# MACH32.net
KiCad netlist of a schematic drawn in EAGLE
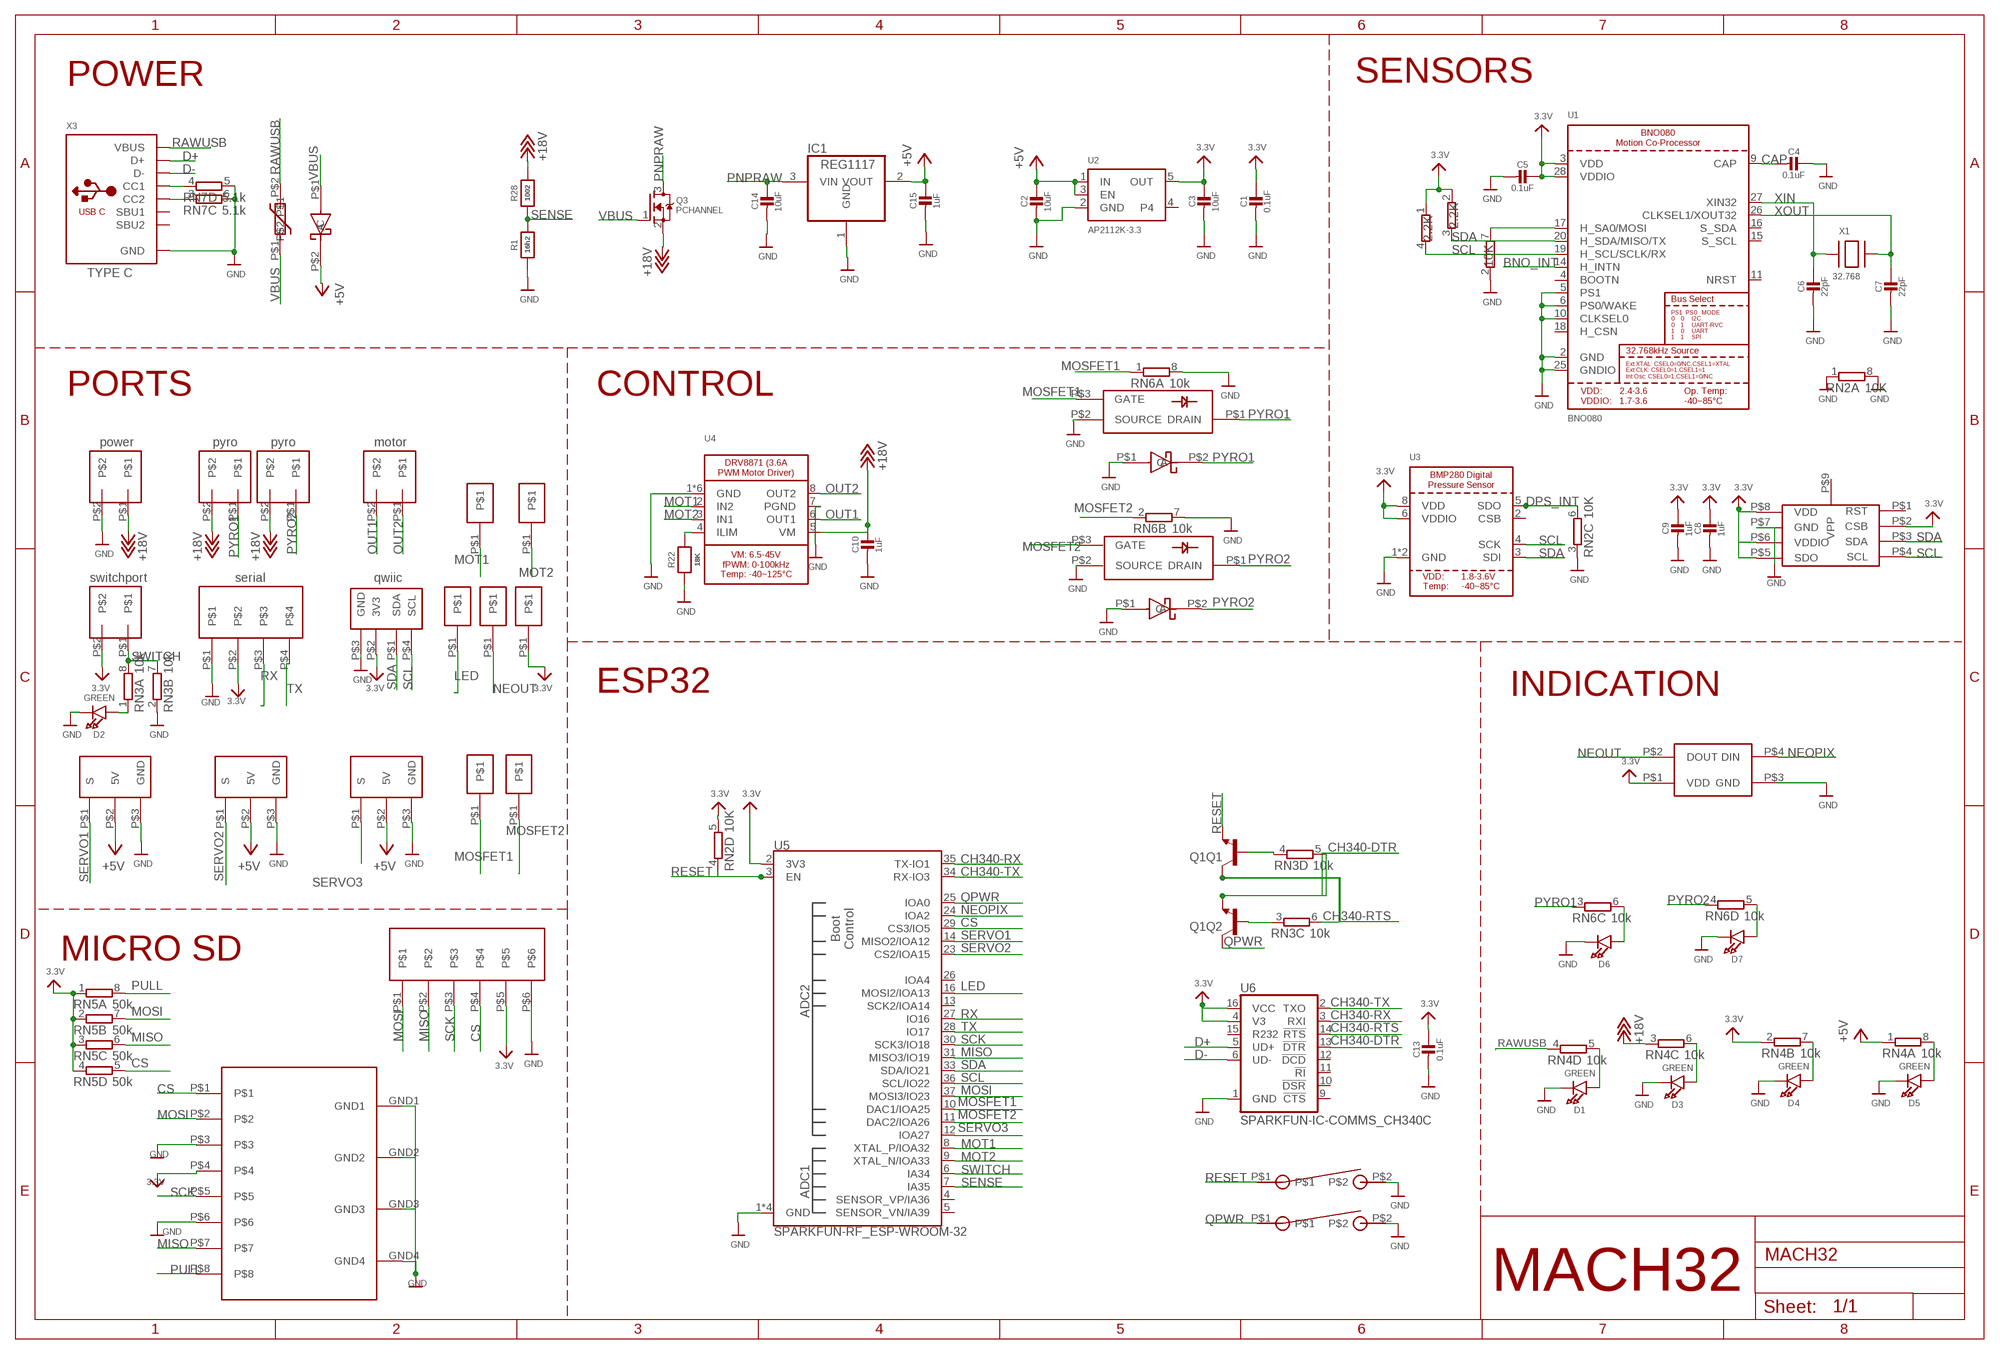
[diagram p0: schematic, sheet 1]

(export (version "E")
  (design (tool "Eeschema 10.0.6"))
  (components
    (comp (ref "C1")
      (value "0.1uF")
      (footprint "eagle-import:0603-NO")
      (libsource (lib "eagle-import") (part "CAP_CERAMIC0603_NO"))
    )
    (comp (ref "C2")
      (value "10uF")
      (footprint "eagle-import:0805-NO")
      (libsource (lib "eagle-import") (part "CAP_CERAMIC0805-NOOUTLINE"))
    )
    (comp (ref "C3")
      (value "10uF")
      (footprint "eagle-import:0805-NO")
      (libsource (lib "eagle-import") (part "CAP_CERAMIC0805-NOOUTLINE"))
    )
    (comp (ref "C4")
      (value "0.1uF")
      (footprint "eagle-import:0603-NO")
      (libsource (lib "eagle-import") (part "CAP_CERAMIC0603_NO"))
    )
    (comp (ref "C5")
      (value "0.1uF")
      (footprint "eagle-import:0603-NO")
      (libsource (lib "eagle-import") (part "CAP_CERAMIC0603_NO"))
    )
    (comp (ref "C6")
      (value "22pF")
      (footprint "eagle-import:0603-NO")
      (libsource (lib "eagle-import") (part "CAP_CERAMIC0603_NO"))
    )
    (comp (ref "C7")
      (value "22pF")
      (footprint "eagle-import:0603-NO")
      (libsource (lib "eagle-import") (part "CAP_CERAMIC0603_NO"))
    )
    (comp (ref "C8")
      (value "1uF")
      (footprint "eagle-import:0603-NO")
      (libsource (lib "eagle-import") (part "CAP_CERAMIC0603_NO"))
    )
    (comp (ref "C9")
      (value "1uF")
      (footprint "eagle-import:0603-NO")
      (libsource (lib "eagle-import") (part "CAP_CERAMIC0603_NO"))
    )
    (comp (ref "C10")
      (value "1uF")
      (footprint "eagle-import:0603-NO")
      (libsource (lib "eagle-import") (part "CAP_CERAMIC0603_NO"))
    )
    (comp (ref "C13")
      (value "0.1uF")
      (footprint "eagle-import:0603-NO")
      (libsource (lib "eagle-import") (part "CAP_CERAMIC0603_NO"))
    )
    (comp (ref "C14")
      (value "10uF")
      (footprint "eagle-import:0805-NO")
      (libsource (lib "eagle-import") (part "CAP_CERAMIC0805-NOOUTLINE"))
    )
    (comp (ref "C15")
      (value "1uF")
      (footprint "eagle-import:0603-NO")
      (libsource (lib "eagle-import") (part "CAP_CERAMIC0603_NO"))
    )
    (comp (ref "D1")
      (value "GREEN")
      (footprint "eagle-import:CHIPLED_0603_NOOUTLINE")
      (libsource (lib "eagle-import") (part "LED0603_NOOUTLINE"))
    )
    (comp (ref "D2")
      (value "GREEN")
      (footprint "eagle-import:CHIPLED_0603_NOOUTLINE")
      (libsource (lib "eagle-import") (part "LED0603_NOOUTLINE"))
    )
    (comp (ref "D3")
      (value "GREEN")
      (footprint "eagle-import:CHIPLED_0603_NOOUTLINE")
      (libsource (lib "eagle-import") (part "LED0603_NOOUTLINE"))
    )
    (comp (ref "D4")
      (value "GREEN")
      (footprint "eagle-import:CHIPLED_0603_NOOUTLINE")
      (libsource (lib "eagle-import") (part "LED0603_NOOUTLINE"))
    )
    (comp (ref "D5")
      (value "GREEN")
      (footprint "eagle-import:CHIPLED_0603_NOOUTLINE")
      (libsource (lib "eagle-import") (part "LED0603_NOOUTLINE"))
    )
    (comp (ref "D6")
      (value "GREEN")
      (footprint "eagle-import:CHIPLED_0603_NOOUTLINE")
      (libsource (lib "eagle-import") (part "LED0603_NOOUTLINE"))
    )
    (comp (ref "D7")
      (value "GREEN")
      (footprint "eagle-import:CHIPLED_0603_NOOUTLINE")
      (fields (field (name "SPICEPREFIX") "D"))
      (libsource (lib "eagle-import") (part "LED0603_NOOUTLINE"))
    )
    (comp (ref "GENERALDIODE")
      (value "PG-TSDSON-8-32")
      (footprint "eagle-import:BSZ036NE2LSATMA1")
      (libsource (lib "eagle-import") (part "PG-TSDSON-8-32"))
    )
    (comp (ref "GENERALDIODE2")
      (value "PG-TSDSON-8-32")
      (footprint "eagle-import:BSZ036NE2LSATMA1")
      (libsource (lib "eagle-import") (part "PG-TSDSON-8-32"))
    )
    (comp (ref "IC1")
      (value "REG1117")
      (footprint "eagle-import:SOT223")
      (libsource (lib "eagle-import") (part "REG1117"))
    )
    (comp (ref "Q1")
      (value "SPARKFUN-DISCRETESEMI_TRANS_NPN_DUAL-MBT3904DW1T1")
      (footprint "eagle-import:SPARKFUN-DISCRETESEMI_SC70-6")
      (libsource (lib "eagle-import") (part "SPARKFUN-DISCRETESEMI_TRANS_NPN_DUAL-MBT3904DW1T1"))
    )
    (comp (ref "Q3")
      (value "PCHANNEL")
      (footprint "eagle-import:SOT23")
      (libsource (lib "eagle-import") (part "MOSFET-NREFLOW"))
    )
    (comp (ref "R1")
      (value "16h2")
      (footprint "eagle-import:MICROBUILDER__1206MP")
      (libsource (lib "eagle-import") (part "MICROBUILDER_RESISTOR_1206MP"))
    )
    (comp (ref "R22")
      (value "18K")
      (footprint "eagle-import:MICROBUILDER__0603MP")
      (libsource (lib "eagle-import") (part "MICROBUILDER_RESISTOR_0603MP"))
    )
    (comp (ref "R28")
      (value "1002")
      (footprint "eagle-import:MICROBUILDER__1206MP")
      (libsource (lib "eagle-import") (part "MICROBUILDER_RESISTOR_1206MP"))
    )
    (comp (ref "RN1")
      (value "2.2K")
      (footprint "eagle-import:EXB34V")
      (libsource (lib "eagle-import") (part "2R-NEXB34V"))
    )
    (comp (ref "RN2")
      (value "10K")
      (footprint "eagle-import:EXB38V")
      (libsource (lib "eagle-import") (part "4R-NEXB38V"))
    )
    (comp (ref "RN3")
      (value "10k")
      (footprint "eagle-import:EXB38V")
      (fields (field (name "SPICEPREFIX") "R"))
      (libsource (lib "eagle-import") (part "4R-NEXB38V"))
    )
    (comp (ref "RN4")
      (value "10k")
      (footprint "eagle-import:EXB38V")
      (libsource (lib "eagle-import") (part "4R-NEXB38V"))
    )
    (comp (ref "RN5")
      (value "50k")
      (footprint "eagle-import:EXB38V")
      (fields (field (name "SPICEPREFIX") "R"))
      (libsource (lib "eagle-import") (part "4R-NEXB38V"))
    )
    (comp (ref "RN6")
      (value "10k")
      (footprint "eagle-import:EXB38V")
      (libsource (lib "eagle-import") (part "4R-NEXB38V"))
    )
    (comp (ref "RN7")
      (value "5.1k")
      (footprint "eagle-import:EXB38V")
      (libsource (lib "eagle-import") (part "4R-NEXB38V"))
    )
    (comp (ref "U$17")
      (value "2SMPB-02E")
      (footprint "eagle-import:2021")
      (libsource (lib "eagle-import") (part "2SMPB-02E"))
    )
    (comp (ref "U$25")
      (value "OSTTEXX0104")
      (footprint "eagle-import:OSTTEXX0104")
      (fields (field (name "SPICEPREFIX") "B"))
      (libsource (lib "eagle-import") (part "OSTTEXX0104"))
    )
    (comp (ref "U$27")
      (value "OSTTEXX0104")
      (footprint "eagle-import:OSTTEXX0104")
      (libsource (lib "eagle-import") (part "OSTTEXX0104"))
    )
    (comp (ref "U$28")
      (value "OSTTEXX0104")
      (footprint "eagle-import:OSTTEXX0104")
      (libsource (lib "eagle-import") (part "OSTTEXX0104"))
    )
    (comp (ref "U$30")
      (value "OSTTEXX0104")
      (footprint "eagle-import:OSTTEXX0104")
      (libsource (lib "eagle-import") (part "OSTTEXX0104"))
    )
    (comp (ref "U$31")
      (value "DF3-4")
      (footprint "eagle-import:DF3-4")
      (libsource (lib "eagle-import") (part "DF3-4"))
    )
    (comp (ref "U$32")
      (value "QWIIC")
      (footprint "eagle-import:QWIIC_V")
      (libsource (lib "eagle-import") (part "QWIIC"))
    )
    (comp (ref "U$34")
      (value "OSTTEXX0104")
      (footprint "eagle-import:OSTTEXX0104")
      (libsource (lib "eagle-import") (part "OSTTEXX0104"))
    )
    (comp (ref "U$47")
      (value "PTC")
      (footprint "eagle-import:1210PTC")
      (libsource (lib "eagle-import") (part "PTC"))
    )
    (comp (ref "U$48")
      (value "SERVO")
      (footprint "eagle-import:SERVO")
      (libsource (lib "eagle-import") (part "SERVO"))
    )
    (comp (ref "U$49")
      (value "SERVO")
      (footprint "eagle-import:SERVO")
      (libsource (lib "eagle-import") (part "SERVO"))
    )
    (comp (ref "U$50")
      (value "SERVO")
      (footprint "eagle-import:SERVO")
      (libsource (lib "eagle-import") (part "SERVO"))
    )
    (comp (ref "U$51")
      (value "SK681-2020")
      (footprint "eagle-import:SK6812-2020")
      (libsource (lib "eagle-import") (part "SK681-2020"))
    )
    (comp (ref "U$52")
      (value "SS24FL")
      (footprint "eagle-import:XC6220")
      (libsource (lib "eagle-import") (part "SS24FL"))
    )
    (comp (ref "U$53")
      (value "SS24FL")
      (footprint "eagle-import:XC6220")
      (libsource (lib "eagle-import") (part "SS24FL"))
    )
    (comp (ref "U$57")
      (value "MALIPAD")
      (footprint "eagle-import:MALIPAD")
      (libsource (lib "eagle-import") (part "MALIPAD"))
    )
    (comp (ref "U$58")
      (value "MALIPAD")
      (footprint "eagle-import:MALIPAD")
      (libsource (lib "eagle-import") (part "MALIPAD"))
    )
    (comp (ref "U$59")
      (value "MALIPAD")
      (footprint "eagle-import:MALIPAD")
      (libsource (lib "eagle-import") (part "MALIPAD"))
    )
    (comp (ref "U$67")
      (value "DF3-6")
      (footprint "eagle-import:DF3-6")
      (libsource (lib "eagle-import") (part "DF3-6"))
    )
    (comp (ref "U$70")
      (value "ST1W008S4AR1500")
      (footprint "eagle-import:ST1W008S4AR1500")
      (libsource (lib "eagle-import") (part "ST1W008S4AR1500"))
    )
    (comp (ref "U$73")
      (value "OMRONSWITCH")
      (footprint "eagle-import:BUTTONOMRON")
      (libsource (lib "eagle-import") (part "OMRONSWITCH"))
    )
    (comp (ref "U$74")
      (value "OMRONSWITCH")
      (footprint "eagle-import:BUTTONOMRON")
      (libsource (lib "eagle-import") (part "OMRONSWITCH"))
    )
    (comp (ref "U$91")
      (value "SS24FL")
      (footprint "eagle-import:XC6220")
      (libsource (lib "eagle-import") (part "SS24FL"))
    )
    (comp (ref "U$100")
      (value "MALIPAD")
      (footprint "eagle-import:MALIPAD")
      (libsource (lib "eagle-import") (part "MALIPAD"))
    )
    (comp (ref "U$104")
      (value "MALIPAD")
      (footprint "eagle-import:MALIPAD")
      (libsource (lib "eagle-import") (part "MALIPAD"))
    )
    (comp (ref "U$105")
      (value "MALIPAD")
      (footprint "eagle-import:MALIPAD")
      (libsource (lib "eagle-import") (part "MALIPAD"))
    )
    (comp (ref "U$106")
      (value "MALIPAD")
      (footprint "eagle-import:MALIPAD")
      (libsource (lib "eagle-import") (part "MALIPAD"))
    )
    (comp (ref "U1")
      (value "BNO080")
      (footprint "eagle-import:BNO080")
      (libsource (lib "eagle-import") (part "BNO080"))
    )
    (comp (ref "U2")
      (value "AP2112K-3.3")
      (footprint "eagle-import:SOT23-5")
      (libsource (lib "eagle-import") (part "VREG_SOT23-5"))
    )
    (comp (ref "U3")
      (value "BMP280_COMBO")
      (footprint "eagle-import:BMX280_COMBO")
      (libsource (lib "eagle-import") (part "BMP280_COMBO"))
    )
    (comp (ref "U4")
      (value "MICROBUILDER_DRV8871")
      (footprint "eagle-import:MICROBUILDER_HSOP8")
      (libsource (lib "eagle-import") (part "MICROBUILDER_DRV8871"))
    )
    (comp (ref "U5")
      (value "SPARKFUN-RF_ESP-WROOM-32")
      (footprint "eagle-import:SPARKFUN-RF_ESP-WROOM-32")
      (libsource (lib "eagle-import") (part "SPARKFUN-RF_ESP-WROOM-32"))
    )
    (comp (ref "U6")
      (value "SPARKFUN-IC-COMMS_CH340C")
      (footprint "eagle-import:SPARKFUN-IC-COMMS_SO016")
      (libsource (lib "eagle-import") (part "SPARKFUN-IC-COMMS_CH340C"))
    )
    (comp (ref "X1")
      (value "32.768")
      (footprint "eagle-import:XTAL3215")
      (libsource (lib "eagle-import") (part "XTAL-3.2X1.5"))
    )
    (comp (ref "X3")
      (value "MICROBUILDER_USB_C")
      (footprint "eagle-import:MICROBUILDER_USB_C_CUSB31-CFM2AX-01-X")
      (libsource (lib "eagle-import") (part "MICROBUILDER_USB_C"))
    )
  )
  (nets
    (net (code "1") (name "+5V") (class "Default")
      (node (ref "C15") (pin "1") (pinfunction "1_1") (pintype "passive"))
      (node (ref "C2") (pin "1") (pinfunction "1_1") (pintype "passive"))
      (node (ref "IC1") (pin "2") (pinfunction "VOUT_2") (pintype "output"))
      (node (ref "RN4") (pin "1") (pinfunction "1_1") (pintype "passive"))
      (node (ref "U$48") (pin "P$2") (pinfunction "5V_P$2") (pintype "bidirectional"))
      (node (ref "U$49") (pin "P$2") (pinfunction "5V_P$2") (pintype "bidirectional"))
      (node (ref "U$50") (pin "P$2") (pinfunction "5V_P$2") (pintype "bidirectional"))
      (node (ref "U$91") (pin "P$2") (pinfunction "C_P$2") (pintype "bidirectional"))
      (node (ref "U2") (pin "1") (pinfunction "IN_1") (pintype "power_in"))
      (node (ref "U2") (pin "3") (pinfunction "EN_3") (pintype "input"))
    )
    (net (code "2") (name "+18V") (class "Default")
      (node (ref "C10") (pin "1") (pinfunction "1_1") (pintype "passive"))
      (node (ref "Q3") (pin "2") (pinfunction "S_2") (pintype "bidirectional"))
      (node (ref "R28") (pin "2") (pinfunction "2_2") (pintype "passive"))
      (node (ref "RN4") (pin "3") (pinfunction "1_3") (pintype "passive"))
      (node (ref "U$25") (pin "P$1") (pinfunction "P$1_P$1") (pintype "bidirectional"))
      (node (ref "U$27") (pin "P$2") (pinfunction "P$2_P$2") (pintype "bidirectional"))
      (node (ref "U$30") (pin "P$2") (pinfunction "P$2_P$2") (pintype "bidirectional"))
      (node (ref "U4") (pin "5") (pinfunction "VM_5") (pintype "power_in"))
    )
    (net (code "3") (name "/BNO_INT") (class "Default")
      (node (ref "U1") (pin "14") (pinfunction "H_INTN_14") (pintype "output"))
    )
    (net (code "4") (name "/CAP") (class "Default")
      (node (ref "C4") (pin "2") (pinfunction "2_2") (pintype "passive"))
      (node (ref "U1") (pin "9") (pinfunction "CAP_9") (pintype "passive"))
    )
    (net (code "5") (name "/CH340-DTR") (class "Default")
      (node (ref "Q1") (pin "1") (pinfunction "E_1") (pintype "passive"))
      (node (ref "RN3") (pin "5") (pinfunction "2_5") (pintype "passive"))
      (node (ref "U6") (pin "13") (pinfunction "~{DTR}_13") (pintype "bidirectional"))
    )
    (net (code "6") (name "/CH340-RTS") (class "Default")
      (node (ref "Q1") (pin "3") (pinfunction "C_3") (pintype "passive"))
      (node (ref "RN3") (pin "6") (pinfunction "2_6") (pintype "passive"))
      (node (ref "U6") (pin "14") (pinfunction "~{RTS}_14") (pintype "bidirectional"))
    )
    (net (code "7") (name "/CH340-RX") (class "Default")
      (node (ref "U5") (pin "35") (pinfunction "TX-IO1_35") (pintype "bidirectional"))
      (node (ref "U6") (pin "3") (pinfunction "RXI_3") (pintype "bidirectional"))
    )
    (net (code "8") (name "/CH340-TX") (class "Default")
      (node (ref "U5") (pin "34") (pinfunction "RX-IO3_34") (pintype "bidirectional"))
      (node (ref "U6") (pin "2") (pinfunction "TXO_2") (pintype "bidirectional"))
    )
    (net (code "9") (name "/CS") (class "Default")
      (node (ref "RN5") (pin "5") (pinfunction "2_5") (pintype "passive"))
      (node (ref "U$67") (pin "P$4") (pinfunction "P$4_P$4") (pintype "bidirectional"))
      (node (ref "U$70") (pin "P$1") (pinfunction "P$1_P$1") (pintype "bidirectional"))
      (node (ref "U5") (pin "29") (pinfunction "CS3/IO5_29") (pintype "bidirectional"))
    )
    (net (code "10") (name "/D+") (class "Default")
      (node (ref "U6") (pin "5") (pinfunction "UD+_5") (pintype "bidirectional"))
      (node (ref "X3") (pin "A6") (pinfunction "D+_A6") (pintype "bidirectional"))
      (node (ref "X3") (pin "B6") (pinfunction "D+_B6") (pintype "bidirectional"))
    )
    (net (code "11") (name "/D-") (class "Default")
      (node (ref "U6") (pin "6") (pinfunction "UD-_6") (pintype "bidirectional"))
      (node (ref "X3") (pin "A7") (pinfunction "D-_A7") (pintype "bidirectional"))
      (node (ref "X3") (pin "B7") (pinfunction "D-_B7") (pintype "bidirectional"))
    )
    (net (code "12") (name "/DPS_INT") (class "Default")
      (node (ref "RN2") (pin "6") (pinfunction "2_6") (pintype "passive"))
      (node (ref "U3") (pin "5") (pinfunction "SDO_5") (pintype "output"))
    )
    (net (code "13") (name "/LED") (class "Default")
      (node (ref "U$59") (pin "P$1") (pinfunction "P$1_P$1") (pintype "bidirectional"))
      (node (ref "U5") (pin "16") (pinfunction "MOSI2/IOA13_16") (pintype "bidirectional"))
    )
    (net (code "14") (name "/MISO") (class "Default")
      (node (ref "RN5") (pin "6") (pinfunction "2_6") (pintype "passive"))
      (node (ref "U$67") (pin "P$2") (pinfunction "P$2_P$2") (pintype "bidirectional"))
      (node (ref "U$70") (pin "P$7") (pinfunction "P$7_P$7") (pintype "bidirectional"))
      (node (ref "U5") (pin "31") (pinfunction "MISO3/IO19_31") (pintype "bidirectional"))
    )
    (net (code "15") (name "/MOSFET1") (class "Default")
      (node (ref "GENERALDIODE") (pin "P$3") (pinfunction "GATE_P$3") (pintype "bidirectional"))
      (node (ref "RN6") (pin "1") (pinfunction "1_1") (pintype "passive"))
      (node (ref "U$100") (pin "P$1") (pinfunction "P$1_P$1") (pintype "bidirectional"))
      (node (ref "U5") (pin "10") (pinfunction "DAC1/IOA25_10") (pintype "bidirectional"))
    )
    (net (code "16") (name "/MOSFET2") (class "Default")
      (node (ref "GENERALDIODE2") (pin "P$3") (pinfunction "GATE_P$3") (pintype "bidirectional"))
      (node (ref "RN6") (pin "2") (pinfunction "1_2") (pintype "passive"))
      (node (ref "U$104") (pin "P$1") (pinfunction "P$1_P$1") (pintype "bidirectional"))
      (node (ref "U5") (pin "11") (pinfunction "DAC2/IOA26_11") (pintype "bidirectional"))
    )
    (net (code "17") (name "/MOSI") (class "Default")
      (node (ref "RN5") (pin "7") (pinfunction "2_7") (pintype "passive"))
      (node (ref "U$67") (pin "P$1") (pinfunction "P$1_P$1") (pintype "bidirectional"))
      (node (ref "U$70") (pin "P$2") (pinfunction "P$2_P$2") (pintype "bidirectional"))
      (node (ref "U5") (pin "37") (pinfunction "MOSI3/IO23_37") (pintype "bidirectional"))
    )
    (net (code "18") (name "/MOT1") (class "Default")
      (node (ref "U$105") (pin "P$1") (pinfunction "P$1_P$1") (pintype "bidirectional"))
      (node (ref "U4") (pin "2") (pinfunction "IN2_2") (pintype "input"))
      (node (ref "U5") (pin "8") (pinfunction "XTAL_P/IOA32_8") (pintype "bidirectional"))
    )
    (net (code "19") (name "/MOT2") (class "Default")
      (node (ref "U$106") (pin "P$1") (pinfunction "P$1_P$1") (pintype "bidirectional"))
      (node (ref "U4") (pin "3") (pinfunction "IN1_3") (pintype "input"))
      (node (ref "U5") (pin "9") (pinfunction "XTAL_N/IOA33_9") (pintype "bidirectional"))
    )
    (net (code "20") (name "/NEOPIX") (class "Default")
      (node (ref "U$51") (pin "P$4") (pinfunction "DIN_P$4") (pintype "bidirectional"))
      (node (ref "U5") (pin "24") (pinfunction "IOA2_24") (pintype "bidirectional"))
    )
    (net (code "21") (name "/NEOUT") (class "Default")
      (node (ref "U$51") (pin "P$2") (pinfunction "DOUT_P$2") (pintype "bidirectional"))
      (node (ref "U$58") (pin "P$1") (pinfunction "P$1_P$1") (pintype "bidirectional"))
    )
    (net (code "22") (name "/OUT1") (class "Default")
      (node (ref "U$28") (pin "P$2") (pinfunction "P$2_P$2") (pintype "bidirectional"))
      (node (ref "U4") (pin "6") (pinfunction "OUT1_6") (pintype "output"))
    )
    (net (code "23") (name "/OUT2") (class "Default")
      (node (ref "U$28") (pin "P$1") (pinfunction "P$1_P$1") (pintype "bidirectional"))
      (node (ref "U4") (pin "8") (pinfunction "OUT2_8") (pintype "output"))
    )
    (net (code "24") (name "/PNPRAW") (class "Default")
      (node (ref "C14") (pin "1") (pinfunction "1_1") (pintype "passive"))
      (node (ref "IC1") (pin "3") (pinfunction "VIN_3") (pintype "input"))
      (node (ref "Q3") (pin "3") (pinfunction "D_3") (pintype "bidirectional"))
    )
    (net (code "25") (name "/PULL") (class "Default")
      (node (ref "RN5") (pin "8") (pinfunction "2_8") (pintype "passive"))
      (node (ref "U$70") (pin "P$8") (pinfunction "P$8_P$8") (pintype "bidirectional"))
    )
    (net (code "26") (name "/PYRO1") (class "Default")
      (node (ref "GENERALDIODE") (pin "P$1") (pinfunction "DRAIN_P$1") (pintype "bidirectional"))
      (node (ref "RN6") (pin "3") (pinfunction "1_3") (pintype "passive"))
      (node (ref "U$27") (pin "P$1") (pinfunction "P$1_P$1") (pintype "bidirectional"))
      (node (ref "U$52") (pin "P$2") (pinfunction "C_P$2") (pintype "bidirectional"))
    )
    (net (code "27") (name "/PYRO2") (class "Default")
      (node (ref "GENERALDIODE2") (pin "P$1") (pinfunction "DRAIN_P$1") (pintype "bidirectional"))
      (node (ref "RN6") (pin "4") (pinfunction "1_4") (pintype "passive"))
      (node (ref "U$30") (pin "P$1") (pinfunction "P$1_P$1") (pintype "bidirectional"))
      (node (ref "U$53") (pin "P$2") (pinfunction "C_P$2") (pintype "bidirectional"))
    )
    (net (code "28") (name "/QPWR") (class "Default")
      (node (ref "Q1") (pin "6") (pinfunction "C_6") (pintype "passive"))
      (node (ref "U$73") (pin "P$1") (pinfunction "P$1_P$1") (pintype "bidirectional"))
      (node (ref "U5") (pin "25") (pinfunction "IOA0_25") (pintype "bidirectional"))
    )
    (net (code "29") (name "/RAWUSB") (class "Default")
      (node (ref "RN4") (pin "4") (pinfunction "1_4") (pintype "passive"))
      (node (ref "U$47") (pin "P$2") (pinfunction "P$2_P$2") (pintype "bidirectional"))
      (node (ref "X3") (pin "A4B9") (pinfunction "VBUS_A4B9") (pintype "power_in"))
      (node (ref "X3") (pin "B4A9") (pinfunction "VBUS_B4A9") (pintype "power_in"))
    )
    (net (code "30") (name "/RESET") (class "Default")
      (node (ref "Q1") (pin "4") (pinfunction "E_4") (pintype "passive"))
      (node (ref "RN2") (pin "4") (pinfunction "1_4") (pintype "passive"))
      (node (ref "U$74") (pin "P$1") (pinfunction "P$1_P$1") (pintype "bidirectional"))
      (node (ref "U5") (pin "3") (pinfunction "EN_3") (pintype "bidirectional"))
    )
    (net (code "31") (name "/RX") (class "Default")
      (node (ref "U$31") (pin "P$3") (pinfunction "P$3_P$3") (pintype "bidirectional"))
      (node (ref "U5") (pin "27") (pinfunction "IO16_27") (pintype "bidirectional"))
    )
    (net (code "32") (name "/SCK") (class "Default")
      (node (ref "U$67") (pin "P$3") (pinfunction "P$3_P$3") (pintype "bidirectional"))
      (node (ref "U$70") (pin "P$5") (pinfunction "P$5_P$5") (pintype "bidirectional"))
      (node (ref "U5") (pin "30") (pinfunction "SCK3/IO18_30") (pintype "bidirectional"))
    )
    (net (code "33") (name "/SCL") (class "Default")
      (node (ref "RN1") (pin "4") (pinfunction "2_4") (pintype "passive"))
      (node (ref "U$17") (pin "P$4") (pinfunction "SCL_P$4") (pintype "bidirectional"))
      (node (ref "U$32") (pin "P$4") (pinfunction "SCL_P$4") (pintype "bidirectional"))
      (node (ref "U1") (pin "19") (pinfunction "H_SCL/SCLK/RX_19") (pintype "bidirectional"))
      (node (ref "U3") (pin "4") (pinfunction "SCK_4") (pintype "input"))
      (node (ref "U5") (pin "36") (pinfunction "SCL/IO22_36") (pintype "bidirectional"))
    )
    (net (code "34") (name "/SDA") (class "Default")
      (node (ref "RN1") (pin "3") (pinfunction "2_3") (pintype "passive"))
      (node (ref "U$17") (pin "P$3") (pinfunction "SDA_P$3") (pintype "bidirectional"))
      (node (ref "U$32") (pin "P$1") (pinfunction "SDA_P$1") (pintype "bidirectional"))
      (node (ref "U1") (pin "20") (pinfunction "H_SDA/MISO/TX_20") (pintype "bidirectional"))
      (node (ref "U3") (pin "3") (pinfunction "SDI_3") (pintype "input"))
      (node (ref "U5") (pin "33") (pinfunction "SDA/IO21_33") (pintype "bidirectional"))
    )
    (net (code "35") (name "/SENSE") (class "Default")
      (node (ref "R1") (pin "2") (pinfunction "2_2") (pintype "passive"))
      (node (ref "R28") (pin "1") (pinfunction "1_1") (pintype "passive"))
      (node (ref "U5") (pin "7") (pinfunction "IA35_7") (pintype "bidirectional"))
    )
    (net (code "36") (name "/SERVO1") (class "Default")
      (node (ref "U$48") (pin "P$1") (pinfunction "S_P$1") (pintype "bidirectional"))
      (node (ref "U5") (pin "14") (pinfunction "MISO2/IOA12_14") (pintype "bidirectional"))
    )
    (net (code "37") (name "/SERVO2") (class "Default")
      (node (ref "U$49") (pin "P$1") (pinfunction "S_P$1") (pintype "bidirectional"))
      (node (ref "U5") (pin "23") (pinfunction "CS2/IOA15_23") (pintype "bidirectional"))
    )
    (net (code "38") (name "/SERVO3") (class "Default")
      (node (ref "U$50") (pin "P$1") (pinfunction "S_P$1") (pintype "bidirectional"))
      (node (ref "U5") (pin "12") (pinfunction "IOA27_12") (pintype "bidirectional"))
    )
    (net (code "39") (name "/SWITCH") (class "Default")
      (node (ref "RN3") (pin "7") (pinfunction "2_7") (pintype "passive"))
      (node (ref "RN3") (pin "8") (pinfunction "2_8") (pintype "passive"))
      (node (ref "U$34") (pin "P$1") (pinfunction "P$1_P$1") (pintype "bidirectional"))
      (node (ref "U5") (pin "6") (pinfunction "IA34_6") (pintype "bidirectional"))
    )
    (net (code "40") (name "/TX") (class "Default")
      (node (ref "U$31") (pin "P$4") (pinfunction "P$4_P$4") (pintype "bidirectional"))
      (node (ref "U5") (pin "28") (pinfunction "IO17_28") (pintype "bidirectional"))
    )
    (net (code "41") (name "/VBUS") (class "Default")
      (node (ref "Q3") (pin "1") (pinfunction "G_1") (pintype "bidirectional"))
      (node (ref "U$47") (pin "P$1") (pinfunction "P$1_P$1") (pintype "bidirectional"))
      (node (ref "U$91") (pin "P$1") (pinfunction "A_P$1") (pintype "bidirectional"))
    )
    (net (code "42") (name "/XIN") (class "Default")
      (node (ref "C6") (pin "1") (pinfunction "1_1") (pintype "passive"))
      (node (ref "U1") (pin "27") (pinfunction "XIN32_27") (pintype "input"))
      (node (ref "X1") (pin "P$1") (pinfunction "P$1_P$1") (pintype "bidirectional"))
    )
    (net (code "43") (name "/XOUT") (class "Default")
      (node (ref "C7") (pin "1") (pinfunction "1_1") (pintype "passive"))
      (node (ref "U1") (pin "26") (pinfunction "CLKSEL1/XOUT32_26") (pintype "output"))
      (node (ref "X1") (pin "P$2") (pinfunction "P$2_P$2") (pintype "bidirectional"))
    )
    (net (code "44") (name "3.3V") (class "Default")
      (node (ref "C1") (pin "1") (pinfunction "1_1") (pintype "passive"))
      (node (ref "C13") (pin "1") (pinfunction "1_1") (pintype "passive"))
      (node (ref "C3") (pin "1") (pinfunction "1_1") (pintype "passive"))
      (node (ref "C5") (pin "1") (pinfunction "1_1") (pintype "passive"))
      (node (ref "C8") (pin "1") (pinfunction "1_1") (pintype "passive"))
      (node (ref "C9") (pin "1") (pinfunction "1_1") (pintype "passive"))
      (node (ref "RN1") (pin "1") (pinfunction "1_1") (pintype "passive"))
      (node (ref "RN1") (pin "2") (pinfunction "1_2") (pintype "passive"))
      (node (ref "RN2") (pin "5") (pinfunction "2_5") (pintype "passive"))
      (node (ref "RN4") (pin "2") (pinfunction "1_2") (pintype "passive"))
      (node (ref "RN5") (pin "1") (pinfunction "1_1") (pintype "passive"))
      (node (ref "RN5") (pin "2") (pinfunction "1_2") (pintype "passive"))
      (node (ref "RN5") (pin "3") (pinfunction "1_3") (pintype "passive"))
      (node (ref "RN5") (pin "4") (pinfunction "1_4") (pintype "passive"))
      (node (ref "U$17") (pin "P$2") (pinfunction "CSB_P$2") (pintype "bidirectional"))
      (node (ref "U$17") (pin "P$5") (pinfunction "SDO_P$5") (pintype "bidirectional"))
      (node (ref "U$17") (pin "P$6") (pinfunction "VDDIO_P$6") (pintype "bidirectional"))
      (node (ref "U$17") (pin "P$8") (pinfunction "VDD_P$8") (pintype "bidirectional"))
      (node (ref "U$31") (pin "P$2") (pinfunction "P$2_P$2") (pintype "bidirectional"))
      (node (ref "U$32") (pin "P$2") (pinfunction "3V3_P$2") (pintype "bidirectional"))
      (node (ref "U$34") (pin "P$2") (pinfunction "P$2_P$2") (pintype "bidirectional"))
      (node (ref "U$51") (pin "P$1") (pinfunction "VDD_P$1") (pintype "bidirectional"))
      (node (ref "U$57") (pin "P$1") (pinfunction "P$1_P$1") (pintype "bidirectional"))
      (node (ref "U$67") (pin "P$5") (pinfunction "P$5_P$5") (pintype "bidirectional"))
      (node (ref "U$70") (pin "P$4") (pinfunction "P$4_P$4") (pintype "bidirectional"))
      (node (ref "U1") (pin "28") (pinfunction "VDDIO_28") (pintype "power_in"))
      (node (ref "U1") (pin "3") (pinfunction "VDD_3") (pintype "power_in"))
      (node (ref "U2") (pin "5") (pinfunction "OUT_5") (pintype "power_in"))
      (node (ref "U3") (pin "6") (pinfunction "VDDIO_6") (pintype "power_in"))
      (node (ref "U3") (pin "8") (pinfunction "VDD_8") (pintype "power_in"))
      (node (ref "U5") (pin "2") (pinfunction "3V3_2") (pintype "bidirectional"))
      (node (ref "U6") (pin "16") (pinfunction "VCC_16") (pintype "bidirectional"))
      (node (ref "U6") (pin "4") (pinfunction "V3_4") (pintype "bidirectional"))
    )
    (net (code "45") (name "GND") (class "Default")
      (node (ref "C1") (pin "2") (pinfunction "2_2") (pintype "passive"))
      (node (ref "C10") (pin "2") (pinfunction "2_2") (pintype "passive"))
      (node (ref "C13") (pin "2") (pinfunction "2_2") (pintype "passive"))
      (node (ref "C14") (pin "2") (pinfunction "2_2") (pintype "passive"))
      (node (ref "C15") (pin "2") (pinfunction "2_2") (pintype "passive"))
      (node (ref "C2") (pin "2") (pinfunction "2_2") (pintype "passive"))
      (node (ref "C3") (pin "2") (pinfunction "2_2") (pintype "passive"))
      (node (ref "C4") (pin "1") (pinfunction "1_1") (pintype "passive"))
      (node (ref "C5") (pin "2") (pinfunction "2_2") (pintype "passive"))
      (node (ref "C6") (pin "2") (pinfunction "2_2") (pintype "passive"))
      (node (ref "C7") (pin "2") (pinfunction "2_2") (pintype "passive"))
      (node (ref "C8") (pin "2") (pinfunction "2_2") (pintype "passive"))
      (node (ref "C9") (pin "2") (pinfunction "2_2") (pintype "passive"))
      (node (ref "D1") (pin "C") (pinfunction "C_C") (pintype "passive"))
      (node (ref "D2") (pin "C") (pinfunction "C_C") (pintype "passive"))
      (node (ref "D3") (pin "C") (pinfunction "C_C") (pintype "passive"))
      (node (ref "D4") (pin "C") (pinfunction "C_C") (pintype "passive"))
      (node (ref "D5") (pin "C") (pinfunction "C_C") (pintype "passive"))
      (node (ref "D6") (pin "C") (pinfunction "C_C") (pintype "passive"))
      (node (ref "D7") (pin "C") (pinfunction "C_C") (pintype "passive"))
      (node (ref "GENERALDIODE") (pin "P$2") (pinfunction "SOURCE_P$2") (pintype "bidirectional"))
      (node (ref "GENERALDIODE2") (pin "P$2") (pinfunction "SOURCE_P$2") (pintype "bidirectional"))
      (node (ref "IC1") (pin "1") (pinfunction "GND_1") (pintype "power_in"))
      (node (ref "R1") (pin "1") (pinfunction "1_1") (pintype "passive"))
      (node (ref "R22") (pin "1") (pinfunction "1_1") (pintype "passive"))
      (node (ref "RN2") (pin "1") (pinfunction "1_1") (pintype "passive"))
      (node (ref "RN2") (pin "2") (pinfunction "1_2") (pintype "passive"))
      (node (ref "RN2") (pin "3") (pinfunction "1_3") (pintype "passive"))
      (node (ref "RN2") (pin "8") (pinfunction "2_8") (pintype "passive"))
      (node (ref "RN3") (pin "2") (pinfunction "1_2") (pintype "passive"))
      (node (ref "RN6") (pin "7") (pinfunction "2_7") (pintype "passive"))
      (node (ref "RN6") (pin "8") (pinfunction "2_8") (pintype "passive"))
      (node (ref "RN7") (pin "5") (pinfunction "2_5") (pintype "passive"))
      (node (ref "RN7") (pin "6") (pinfunction "2_6") (pintype "passive"))
      (node (ref "U$17") (pin "P$7") (pinfunction "GND_P$7") (pintype "bidirectional"))
      (node (ref "U$25") (pin "P$2") (pinfunction "P$2_P$2") (pintype "bidirectional"))
      (node (ref "U$31") (pin "P$1") (pinfunction "P$1_P$1") (pintype "bidirectional"))
      (node (ref "U$32") (pin "P$3") (pinfunction "GND_P$3") (pintype "bidirectional"))
      (node (ref "U$48") (pin "P$3") (pinfunction "GND_P$3") (pintype "bidirectional"))
      (node (ref "U$49") (pin "P$3") (pinfunction "GND_P$3") (pintype "bidirectional"))
      (node (ref "U$50") (pin "P$3") (pinfunction "GND_P$3") (pintype "bidirectional"))
      (node (ref "U$51") (pin "P$3") (pinfunction "GND_P$3") (pintype "bidirectional"))
      (node (ref "U$52") (pin "P$1") (pinfunction "A_P$1") (pintype "bidirectional"))
      (node (ref "U$53") (pin "P$1") (pinfunction "A_P$1") (pintype "bidirectional"))
      (node (ref "U$67") (pin "P$6") (pinfunction "P$6_P$6") (pintype "bidirectional"))
      (node (ref "U$70") (pin "GND1") (pinfunction "GND1_GND1") (pintype "bidirectional"))
      (node (ref "U$70") (pin "GND2") (pinfunction "GND2_GND2") (pintype "bidirectional"))
      (node (ref "U$70") (pin "GND3") (pinfunction "GND3_GND3") (pintype "bidirectional"))
      (node (ref "U$70") (pin "GND4") (pinfunction "GND4_GND4") (pintype "bidirectional"))
      (node (ref "U$70") (pin "P$3") (pinfunction "P$3_P$3") (pintype "bidirectional"))
      (node (ref "U$70") (pin "P$6") (pinfunction "P$6_P$6") (pintype "bidirectional"))
      (node (ref "U$73") (pin "P$2") (pinfunction "P$2_P$2") (pintype "bidirectional"))
      (node (ref "U$74") (pin "P$2") (pinfunction "P$2_P$2") (pintype "bidirectional"))
      (node (ref "U1") (pin "10") (pinfunction "CLKSEL0_10") (pintype "input"))
      (node (ref "U1") (pin "2") (pinfunction "GND_2") (pintype "power_in"))
      (node (ref "U1") (pin "25") (pinfunction "GNDIO_25") (pintype "power_in"))
      (node (ref "U1") (pin "5") (pinfunction "PS1_5") (pintype "input"))
      (node (ref "U1") (pin "6") (pinfunction "PS0/WAKE_6") (pintype "input"))
      (node (ref "U2") (pin "2") (pinfunction "GND_2") (pintype "power_in"))
      (node (ref "U3") (pin "1") (pinfunction "GND_1") (pintype "power_in"))
      (node (ref "U3") (pin "7") (pinfunction "GND_7") (pintype "power_in"))
      (node (ref "U4") (pin "1") (pinfunction "GND_1") (pintype "power_in"))
      (node (ref "U4") (pin "7") (pinfunction "PGND_7") (pintype "power_in"))
      (node (ref "U4") (pin "GND") (pinfunction "GND_GND") (pintype "power_in"))
      (node (ref "U4") (pin "P$1") (pinfunction "GND_P$1") (pintype "power_in"))
      (node (ref "U4") (pin "P$2") (pinfunction "GND_P$2") (pintype "power_in"))
      (node (ref "U4") (pin "P$3") (pinfunction "GND_P$3") (pintype "power_in"))
      (node (ref "U4") (pin "P$4") (pinfunction "GND_P$4") (pintype "power_in"))
      (node (ref "U5") (pin "1") (pinfunction "GND_1") (pintype "bidirectional"))
      (node (ref "U5") (pin "15") (pinfunction "GND_15") (pintype "bidirectional"))
      (node (ref "U5") (pin "38") (pinfunction "GND_38") (pintype "bidirectional"))
      (node (ref "U5") (pin "GND") (pinfunction "GND_GND") (pintype "bidirectional"))
      (node (ref "U6") (pin "1") (pinfunction "GND_1") (pintype "bidirectional"))
      (node (ref "X3") (pin "A1B12") (pinfunction "GND_A1B12") (pintype "power_in"))
      (node (ref "X3") (pin "B1A12") (pinfunction "GND_B1A12") (pintype "power_in"))
    )
    (net (code "46") (name "Net-(D2-PadA)") (class "Default")
      (node (ref "D2") (pin "A") (pinfunction "A_A") (pintype "passive"))
      (node (ref "RN3") (pin "1") (pinfunction "1_1") (pintype "passive"))
    )
    (net (code "47") (name "Net-(Q1A-B)") (class "Default")
      (node (ref "Q1") (pin "5") (pinfunction "B_5") (pintype "passive"))
      (node (ref "RN3") (pin "4") (pinfunction "1_4") (pintype "passive"))
    )
    (net (code "48") (name "Net-(Q1B-B)") (class "Default")
      (node (ref "Q1") (pin "2") (pinfunction "B_2") (pintype "passive"))
      (node (ref "RN3") (pin "3") (pinfunction "1_3") (pintype "passive"))
    )
    (net (code "49") (name "Net-(RN2B-2)") (class "Default")
      (node (ref "RN2") (pin "7") (pinfunction "2_7") (pintype "passive"))
      (node (ref "U1") (pin "17") (pinfunction "H_SA0/MOSI_17") (pintype "output"))
    )
    (net (code "50") (name "Net-(RN4A-2)") (class "Default")
      (node (ref "D5") (pin "A") (pinfunction "A_A") (pintype "passive"))
      (node (ref "RN4") (pin "8") (pinfunction "2_8") (pintype "passive"))
    )
    (net (code "51") (name "Net-(RN4B-2)") (class "Default")
      (node (ref "D4") (pin "A") (pinfunction "A_A") (pintype "passive"))
      (node (ref "RN4") (pin "7") (pinfunction "2_7") (pintype "passive"))
    )
    (net (code "52") (name "Net-(RN4C-2)") (class "Default")
      (node (ref "D3") (pin "A") (pinfunction "A_A") (pintype "passive"))
      (node (ref "RN4") (pin "6") (pinfunction "2_6") (pintype "passive"))
    )
    (net (code "53") (name "Net-(RN4D-2)") (class "Default")
      (node (ref "D1") (pin "A") (pinfunction "A_A") (pintype "passive"))
      (node (ref "RN4") (pin "5") (pinfunction "2_5") (pintype "passive"))
    )
    (net (code "54") (name "Net-(RN6C-2)") (class "Default")
      (node (ref "D6") (pin "A") (pinfunction "A_A") (pintype "passive"))
      (node (ref "RN6") (pin "6") (pinfunction "2_6") (pintype "passive"))
    )
    (net (code "55") (name "Net-(RN6D-2)") (class "Default")
      (node (ref "D7") (pin "A") (pinfunction "A_A") (pintype "passive"))
      (node (ref "RN6") (pin "5") (pinfunction "2_5") (pintype "passive"))
    )
    (net (code "56") (name "Net-(RN7C-1)") (class "Default")
      (node (ref "RN7") (pin "3") (pinfunction "1_3") (pintype "passive"))
      (node (ref "X3") (pin "B5") (pinfunction "CC2_B5") (pintype "bidirectional"))
    )
    (net (code "57") (name "Net-(RN7D-1)") (class "Default")
      (node (ref "RN7") (pin "4") (pinfunction "1_4") (pintype "passive"))
      (node (ref "X3") (pin "A5") (pinfunction "CC1_A5") (pintype "bidirectional"))
    )
    (net (code "58") (name "Net-(U4-ILIM)") (class "Default")
      (node (ref "R22") (pin "2") (pinfunction "2_2") (pintype "passive"))
      (node (ref "U4") (pin "4") (pinfunction "ILIM_4") (pintype "input"))
    )
    (net (code "59") (name "unconnected-(U$17-RST-PadP$1)") (class "Default")
      (node (ref "U$17") (pin "P$1") (pinfunction "RST_P$1") (pintype "bidirectional"))
    )
    (net (code "60") (name "unconnected-(U$17-VPP-PadP$9)") (class "Default")
      (node (ref "U$17") (pin "P$9") (pinfunction "VPP_P$9") (pintype "bidirectional"))
    )
    (net (code "61") (name "unconnected-(U1-BOOTN-Pad4)") (class "Default")
      (node (ref "U1") (pin "4") (pinfunction "BOOTN_4") (pintype "input"))
    )
    (net (code "62") (name "unconnected-(U1-H_CSN-Pad18)") (class "Default")
      (node (ref "U1") (pin "18") (pinfunction "H_CSN_18") (pintype "input"))
    )
    (net (code "63") (name "unconnected-(U1-NRST-Pad11)") (class "Default")
      (node (ref "U1") (pin "11") (pinfunction "NRST_11") (pintype "input"))
    )
    (net (code "64") (name "unconnected-(U1-S_SCL-Pad15)") (class "Default")
      (node (ref "U1") (pin "15") (pinfunction "S_SCL_15") (pintype "bidirectional"))
    )
    (net (code "65") (name "unconnected-(U1-S_SDA-Pad16)") (class "Default")
      (node (ref "U1") (pin "16") (pinfunction "S_SDA_16") (pintype "bidirectional"))
    )
    (net (code "66") (name "unconnected-(U2-P4-Pad4)") (class "Default")
      (node (ref "U2") (pin "4") (pinfunction "P4_4") (pintype "bidirectional"))
    )
    (net (code "67") (name "unconnected-(U3-CSB-Pad2)") (class "Default")
      (node (ref "U3") (pin "2") (pinfunction "CSB_2") (pintype "input"))
    )
    (net (code "68") (name "unconnected-(U5-IOA4-Pad26)") (class "Default")
      (node (ref "U5") (pin "26") (pinfunction "IOA4_26") (pintype "bidirectional"))
    )
    (net (code "69") (name "unconnected-(U5-SCK2{slash}IOA14-Pad13)") (class "Default")
      (node (ref "U5") (pin "13") (pinfunction "SCK2/IOA14_13") (pintype "bidirectional"))
    )
    (net (code "70") (name "unconnected-(U5-SENSOR_VN{slash}IA39-Pad5)") (class "Default")
      (node (ref "U5") (pin "5") (pinfunction "SENSOR_VN/IA39_5") (pintype "bidirectional"))
    )
    (net (code "71") (name "unconnected-(U5-SENSOR_VP{slash}IA36-Pad4)") (class "Default")
      (node (ref "U5") (pin "4") (pinfunction "SENSOR_VP/IA36_4") (pintype "bidirectional"))
    )
    (net (code "72") (name "unconnected-(U6-R232-Pad15)") (class "Default")
      (node (ref "U6") (pin "15") (pinfunction "R232_15") (pintype "bidirectional"))
    )
    (net (code "73") (name "unconnected-(U6-~{CTS}-Pad9)") (class "Default")
      (node (ref "U6") (pin "9") (pinfunction "~{CTS}_9") (pintype "bidirectional"))
    )
    (net (code "74") (name "unconnected-(U6-~{DCD}-Pad12)") (class "Default")
      (node (ref "U6") (pin "12") (pinfunction "~{DCD}_12") (pintype "bidirectional"))
    )
    (net (code "75") (name "unconnected-(U6-~{DSR}-Pad10)") (class "Default")
      (node (ref "U6") (pin "10") (pinfunction "~{DSR}_10") (pintype "bidirectional"))
    )
    (net (code "76") (name "unconnected-(U6-~{RI}-Pad11)") (class "Default")
      (node (ref "U6") (pin "11") (pinfunction "~{RI}_11") (pintype "bidirectional"))
    )
    (net (code "77") (name "unconnected-(X3-SBU1-PadA8)") (class "Default")
      (node (ref "X3") (pin "A8") (pinfunction "SBU1_A8") (pintype "bidirectional"))
    )
    (net (code "78") (name "unconnected-(X3-SBU2-PadB8)") (class "Default")
      (node (ref "X3") (pin "B8") (pinfunction "SBU2_B8") (pintype "bidirectional"))
    )
  )
)
